# MOTOR_DRIVER.net
KiCad netlist of a schematic drawn in Altium Designer
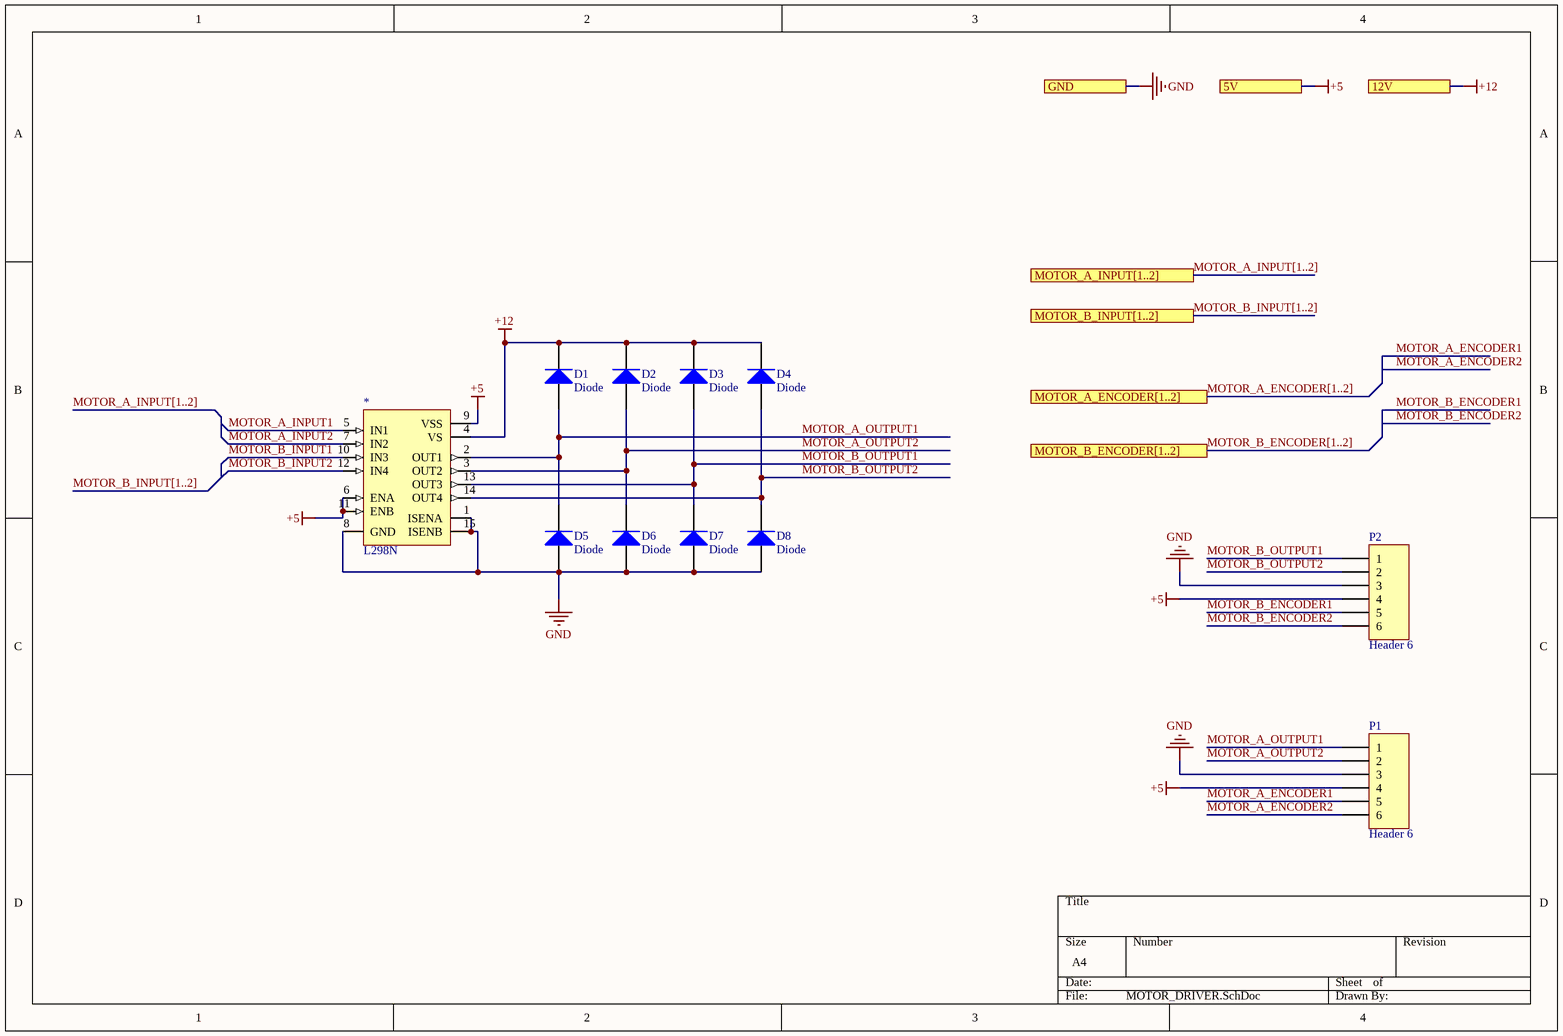
[diagram p0: MOTOR_DRIVER.SchDoc]

(export (version "E")
  (design (tool "Eeschema 10.0.6"))
  (components
    (comp (ref "*") (value "L298N") (footprint "L298N-DIP") (libsource (lib "L298N") (part "L298N")))
    (comp (ref "D1")
      (value "Diode")
      (footprint "MY0805")
      (description "Default Diode")
      (fields (field (name "PUBLISHER") "Altium Limited"))
      (libsource (lib "Miscellaneous Devices") (part "Diode"))
    )
    (comp (ref "D2")
      (value "Diode")
      (footprint "MY0805")
      (description "Default Diode")
      (fields (field (name "PUBLISHER") "Altium Limited"))
      (libsource (lib "Miscellaneous Devices") (part "Diode"))
    )
    (comp (ref "D3")
      (value "Diode")
      (footprint "MY0805")
      (description "Default Diode")
      (fields (field (name "PUBLISHER") "Altium Limited"))
      (libsource (lib "Miscellaneous Devices") (part "Diode"))
    )
    (comp (ref "D4")
      (value "Diode")
      (footprint "MY0805")
      (description "Default Diode")
      (fields (field (name "PUBLISHER") "Altium Limited"))
      (libsource (lib "Miscellaneous Devices") (part "Diode"))
    )
    (comp (ref "D5")
      (value "Diode")
      (footprint "MY0805")
      (description "Default Diode")
      (fields (field (name "PUBLISHER") "Altium Limited"))
      (libsource (lib "Miscellaneous Devices") (part "Diode"))
    )
    (comp (ref "D6")
      (value "Diode")
      (footprint "MY0805")
      (description "Default Diode")
      (fields (field (name "PUBLISHER") "Altium Limited"))
      (libsource (lib "Miscellaneous Devices") (part "Diode"))
    )
    (comp (ref "D7")
      (value "Diode")
      (footprint "MY0805")
      (description "Default Diode")
      (fields (field (name "PUBLISHER") "Altium Limited"))
      (libsource (lib "Miscellaneous Devices") (part "Diode"))
    )
    (comp (ref "D8")
      (value "Diode")
      (footprint "MY0805")
      (description "Default Diode")
      (fields (field (name "PUBLISHER") "Altium Limited"))
      (libsource (lib "Miscellaneous Devices") (part "Diode"))
    )
    (comp (ref "P1")
      (value "Header 6")
      (footprint "HDR1X6")
      (description "Header, 6-Pin")
      (fields (field (name "PUBLISHER") "Altium Limited"))
      (libsource (lib "Miscellaneous Connectors") (part "Header 6"))
    )
    (comp (ref "P2")
      (value "Header 6")
      (footprint "HDR1X6")
      (description "Header, 6-Pin")
      (fields (field (name "PUBLISHER") "Altium Limited"))
      (libsource (lib "Miscellaneous Connectors") (part "Header 6"))
    )
  )
  (nets
    (net (code "1") (name "+5") (class "Default")
      (node (ref "*") (pin "11") (pinfunction "ENB_11") (pintype "input"))
      (node (ref "*") (pin "6") (pinfunction "ENA_6") (pintype "input"))
      (node (ref "*") (pin "9") (pinfunction "VSS_9") (pintype "passive"))
      (node (ref "P1") (pin "4") (pinfunction "4_4") (pintype "passive"))
      (node (ref "P2") (pin "4") (pinfunction "4_4") (pintype "passive"))
    )
    (net (code "2") (name "+12") (class "Default")
      (node (ref "*") (pin "4") (pinfunction "VS_4") (pintype "passive"))
      (node (ref "D1") (pin "2") (pinfunction "K_2") (pintype "passive"))
      (node (ref "D2") (pin "2") (pinfunction "K_2") (pintype "passive"))
      (node (ref "D3") (pin "2") (pinfunction "K_2") (pintype "passive"))
      (node (ref "D4") (pin "2") (pinfunction "K_2") (pintype "passive"))
    )
    (net (code "3") (name "/MOTOR_A_ENCODER1") (class "Default")
      (node (ref "P1") (pin "5") (pinfunction "5_5") (pintype "passive"))
    )
    (net (code "4") (name "/MOTOR_A_ENCODER2") (class "Default")
      (node (ref "P1") (pin "6") (pinfunction "6_6") (pintype "passive"))
    )
    (net (code "6") (name "/MOTOR_A_INPUT1") (class "Default")
      (node (ref "*") (pin "5") (pinfunction "IN1_5") (pintype "input"))
    )
    (net (code "7") (name "/MOTOR_A_INPUT2") (class "Default")
      (node (ref "*") (pin "7") (pinfunction "IN2_7") (pintype "input"))
    )
    (net (code "9") (name "/MOTOR_A_OUTPUT1") (class "Default")
      (node (ref "*") (pin "2") (pinfunction "OUT1_2") (pintype "output"))
      (node (ref "D1") (pin "1") (pinfunction "A_1") (pintype "passive"))
      (node (ref "D5") (pin "2") (pinfunction "K_2") (pintype "passive"))
      (node (ref "P1") (pin "1") (pinfunction "1_1") (pintype "passive"))
    )
    (net (code "10") (name "/MOTOR_A_OUTPUT2") (class "Default")
      (node (ref "*") (pin "3") (pinfunction "OUT2_3") (pintype "output"))
      (node (ref "D2") (pin "1") (pinfunction "A_1") (pintype "passive"))
      (node (ref "D6") (pin "2") (pinfunction "K_2") (pintype "passive"))
      (node (ref "P1") (pin "2") (pinfunction "2_2") (pintype "passive"))
    )
    (net (code "11") (name "/MOTOR_B_ENCODER1") (class "Default")
      (node (ref "P2") (pin "5") (pinfunction "5_5") (pintype "passive"))
    )
    (net (code "12") (name "/MOTOR_B_ENCODER2") (class "Default")
      (node (ref "P2") (pin "6") (pinfunction "6_6") (pintype "passive"))
    )
    (net (code "14") (name "/MOTOR_B_INPUT1") (class "Default")
      (node (ref "*") (pin "10") (pinfunction "IN3_10") (pintype "input"))
    )
    (net (code "15") (name "/MOTOR_B_INPUT2") (class "Default")
      (node (ref "*") (pin "12") (pinfunction "IN4_12") (pintype "input"))
    )
    (net (code "17") (name "/MOTOR_B_OUTPUT1") (class "Default")
      (node (ref "*") (pin "13") (pinfunction "OUT3_13") (pintype "output"))
      (node (ref "D3") (pin "1") (pinfunction "A_1") (pintype "passive"))
      (node (ref "D7") (pin "2") (pinfunction "K_2") (pintype "passive"))
      (node (ref "P2") (pin "1") (pinfunction "1_1") (pintype "passive"))
    )
    (net (code "18") (name "/MOTOR_B_OUTPUT2") (class "Default")
      (node (ref "*") (pin "14") (pinfunction "OUT4_14") (pintype "output"))
      (node (ref "D4") (pin "1") (pinfunction "A_1") (pintype "passive"))
      (node (ref "D8") (pin "2") (pinfunction "K_2") (pintype "passive"))
      (node (ref "P2") (pin "2") (pinfunction "2_2") (pintype "passive"))
    )
    (net (code "19") (name "GND") (class "Default")
      (node (ref "*") (pin "1") (pinfunction "ISENA_1") (pintype "passive"))
      (node (ref "*") (pin "15") (pinfunction "ISENB_15") (pintype "passive"))
      (node (ref "*") (pin "8") (pinfunction "GND_8") (pintype "passive"))
      (node (ref "D5") (pin "1") (pinfunction "A_1") (pintype "passive"))
      (node (ref "D6") (pin "1") (pinfunction "A_1") (pintype "passive"))
      (node (ref "D7") (pin "1") (pinfunction "A_1") (pintype "passive"))
      (node (ref "D8") (pin "1") (pinfunction "A_1") (pintype "passive"))
      (node (ref "P1") (pin "3") (pinfunction "3_3") (pintype "passive"))
      (node (ref "P2") (pin "3") (pinfunction "3_3") (pintype "passive"))
    )
  )
)
